# reel_schematic.net
KiCad netlist of a schematic drawn in EAGLE
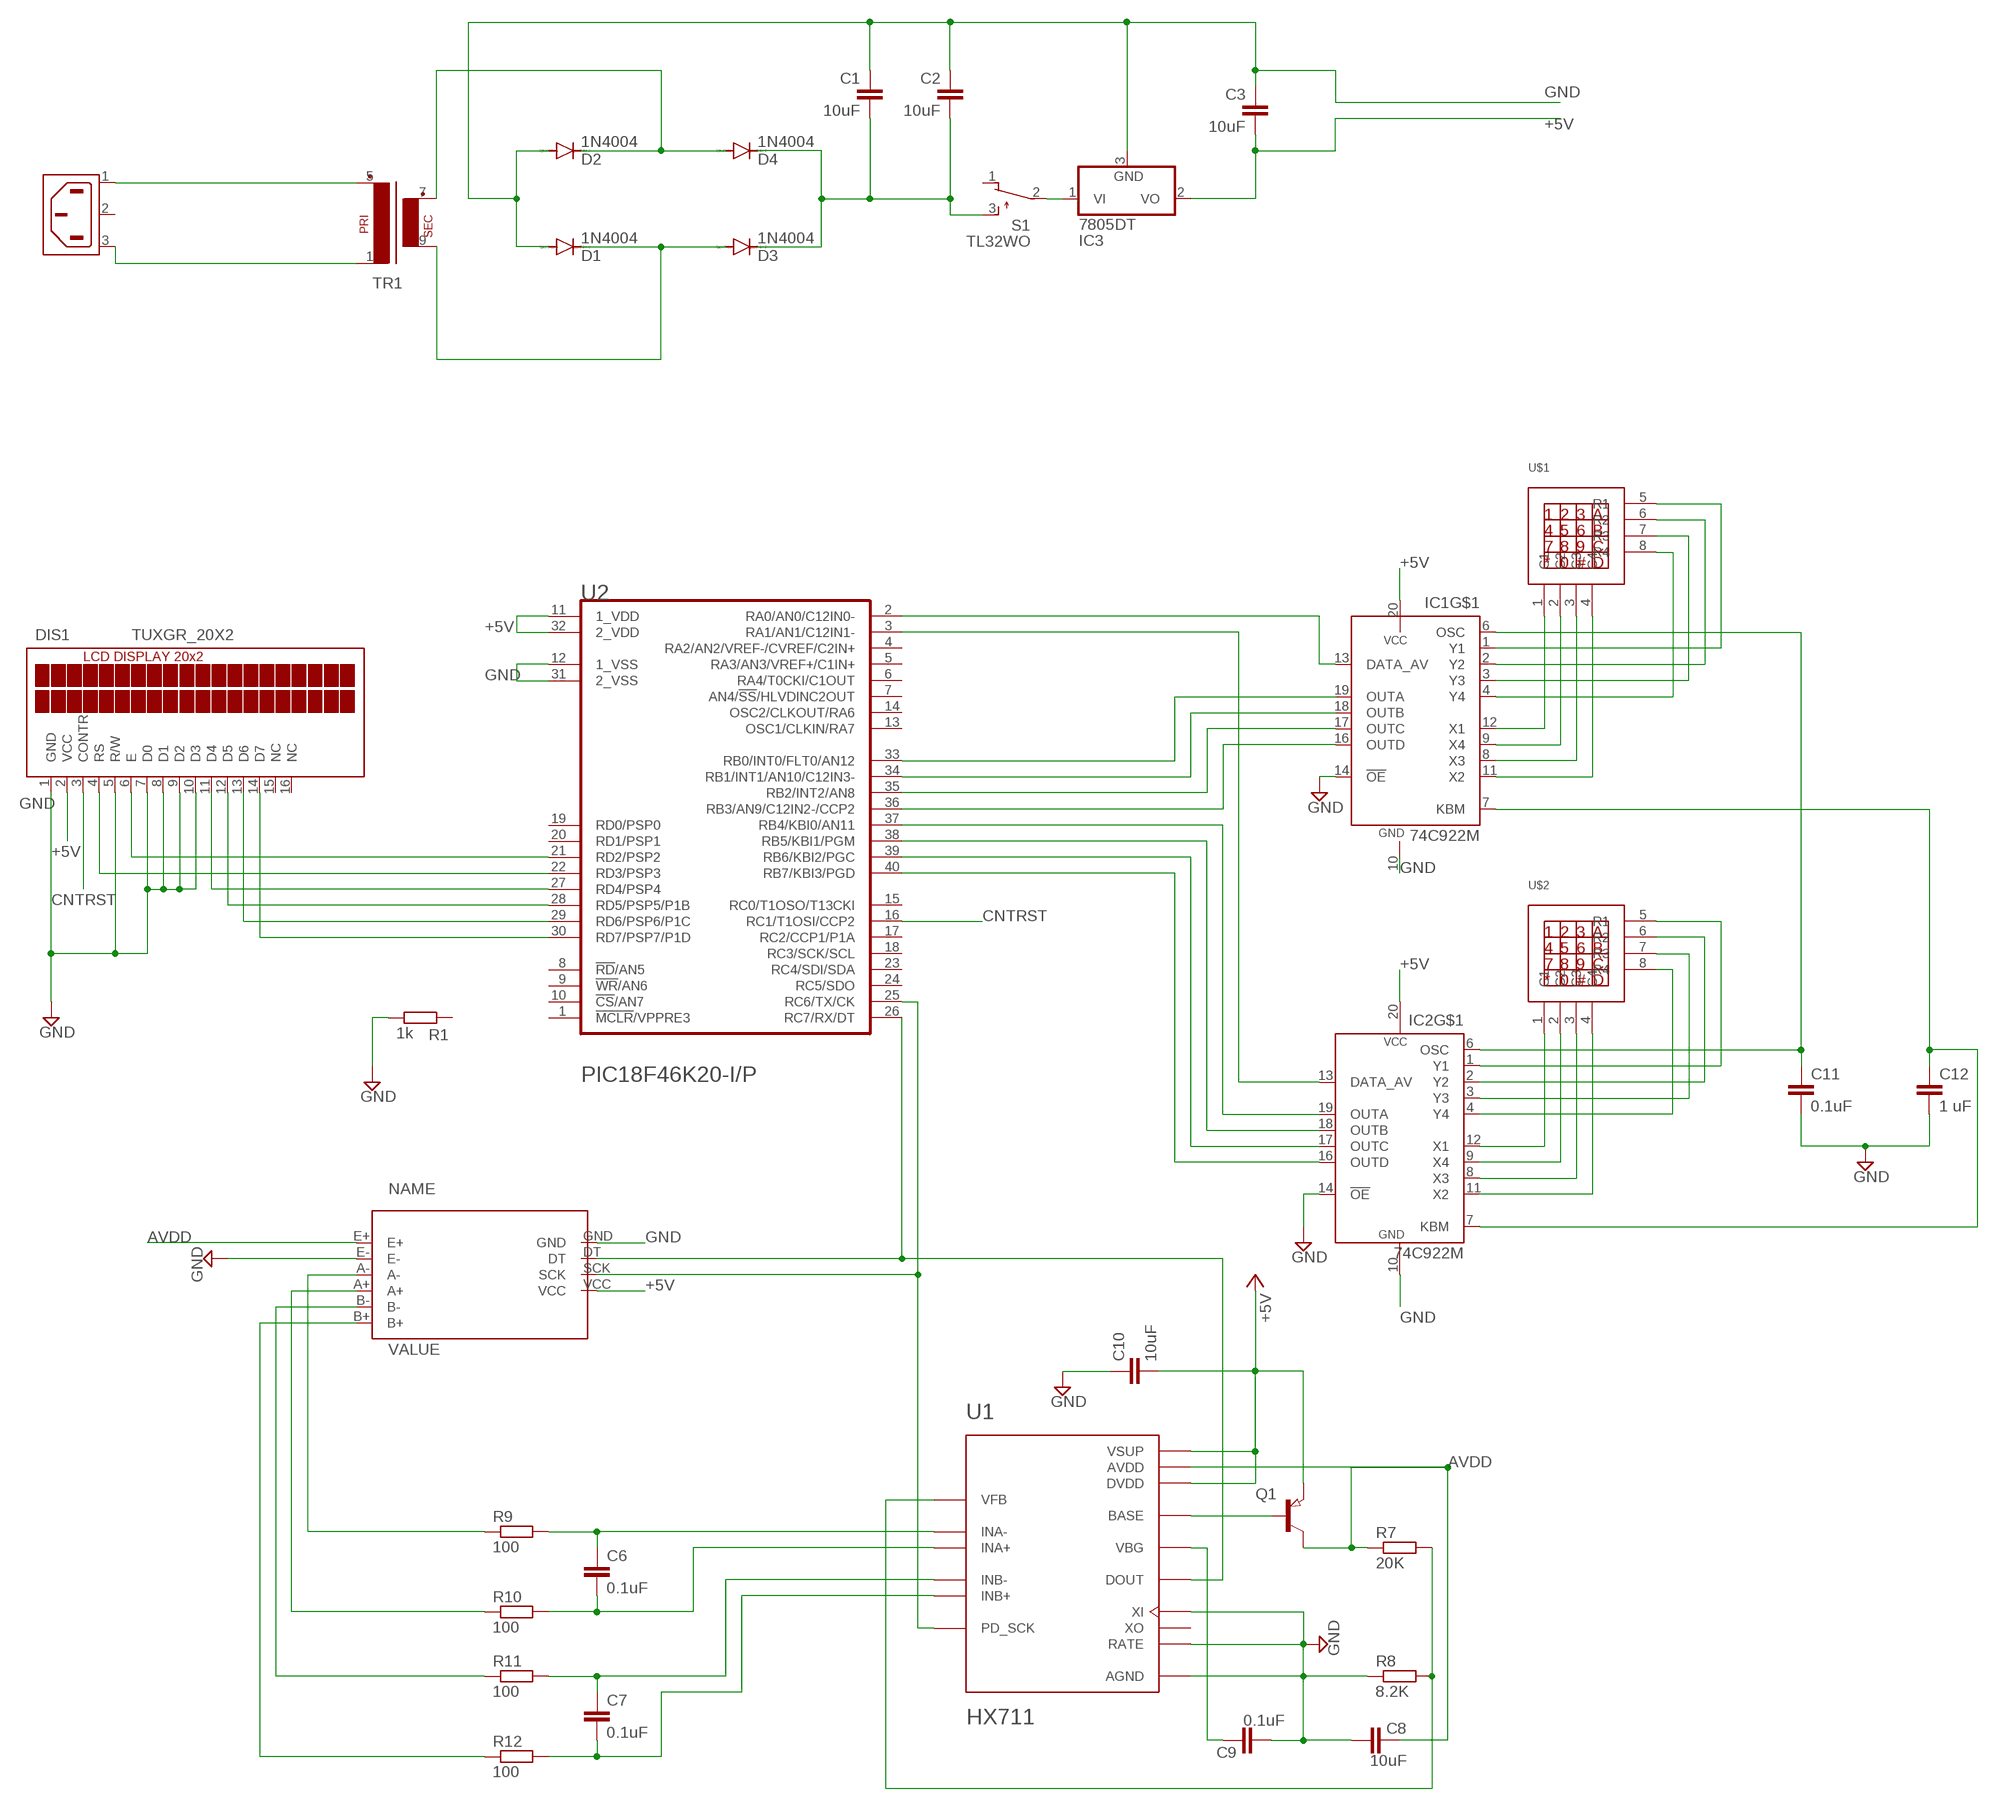
[diagram p0: schematic, sheet 1]

(export (version "E")
  (design (tool "Eeschema 10.0.6"))
  (components
    (comp (ref "C1")
      (value "10uF")
      (footprint "eagle-import:C2.5-2")
      (libsource (lib "eagle-import") (part "C2.5/2"))
    )
    (comp (ref "C2")
      (value "10uF")
      (footprint "eagle-import:C2.5-2")
      (libsource (lib "eagle-import") (part "C2.5/2"))
    )
    (comp (ref "C3")
      (value "10uF")
      (footprint "eagle-import:C2.5-2")
      (libsource (lib "eagle-import") (part "C2.5/2"))
    )
    (comp (ref "C6")
      (value "0.1uF")
      (footprint "eagle-import:C2.5-2")
      (libsource (lib "eagle-import") (part "C2.5/2"))
    )
    (comp (ref "C7")
      (value "0.1uF")
      (footprint "eagle-import:C2.5-2")
      (libsource (lib "eagle-import") (part "C2.5/2"))
    )
    (comp (ref "C8")
      (value "10uF")
      (footprint "eagle-import:C2.5-2")
      (libsource (lib "eagle-import") (part "C2.5/2"))
    )
    (comp (ref "C9")
      (value "0.1uF")
      (footprint "eagle-import:C2.5-2")
      (libsource (lib "eagle-import") (part "C2.5/2"))
    )
    (comp (ref "C10")
      (value "10uF")
      (footprint "eagle-import:C2.5-2")
      (libsource (lib "eagle-import") (part "C2.5/2"))
    )
    (comp (ref "C11")
      (value "0.1uF")
      (footprint "eagle-import:C2.5-2")
      (libsource (lib "eagle-import") (part "C2.5/2"))
    )
    (comp (ref "C12")
      (value "1 uF")
      (footprint "eagle-import:C2.5-2")
      (libsource (lib "eagle-import") (part "C2.5/2"))
    )
    (comp (ref "D1")
      (value "1N4004")
      (footprint "eagle-import:DO41-10")
      (libsource (lib "eagle-import") (part "1N4004"))
    )
    (comp (ref "D2")
      (value "1N4004")
      (footprint "eagle-import:DO41-10")
      (libsource (lib "eagle-import") (part "1N4004"))
    )
    (comp (ref "D3")
      (value "1N4004")
      (footprint "eagle-import:DO41-10")
      (libsource (lib "eagle-import") (part "1N4004"))
    )
    (comp (ref "D4")
      (value "1N4004")
      (footprint "eagle-import:DO41-10")
      (libsource (lib "eagle-import") (part "1N4004"))
    )
    (comp (ref "DIS1")
      (value "TUXGR_20X2")
      (footprint "eagle-import:TUXGR_20X2")
      (libsource (lib "eagle-import") (part "TUXGR_20X2"))
    )
    (comp (ref "HX711MODULE")
      (value "hx")
      (footprint "eagle-import:HX711")
      (libsource (lib "eagle-import") (part "HX711A"))
    )
    (comp (ref "IC1")
      (value "74C922M")
      (footprint "eagle-import:SO20W")
      (libsource (lib "eagle-import") (part "74C922M"))
    )
    (comp (ref "IC2")
      (value "74C922M")
      (footprint "eagle-import:SO20W")
      (libsource (lib "eagle-import") (part "74C922M"))
    )
    (comp (ref "IC3")
      (value "7805DT")
      (footprint "eagle-import:TO252")
      (libsource (lib "eagle-import") (part "78DT05"))
    )
    (comp (ref "Q1")
      (value "PNP-TRANSISTOR_SOT23")
      (footprint "eagle-import:SOT23")
      (libsource (lib "eagle-import") (part "PNP-TRANSISTOR_SOT23"))
    )
    (comp (ref "R1")
      (value "1k")
      (footprint "eagle-import:R0603")
      (libsource (lib "eagle-import") (part "R-EU_R0603"))
    )
    (comp (ref "R7")
      (value "20K")
      (footprint "eagle-import:R0603")
      (libsource (lib "eagle-import") (part "R-EU_R0603"))
    )
    (comp (ref "R8")
      (value "8.2K")
      (footprint "eagle-import:R0603")
      (libsource (lib "eagle-import") (part "R-EU_R0603"))
    )
    (comp (ref "R9")
      (value "100")
      (footprint "eagle-import:R0603")
      (libsource (lib "eagle-import") (part "R-EU_R0603"))
    )
    (comp (ref "R10")
      (value "100")
      (footprint "eagle-import:R0603")
      (libsource (lib "eagle-import") (part "R-EU_R0603"))
    )
    (comp (ref "R11")
      (value "100")
      (footprint "eagle-import:R0603")
      (libsource (lib "eagle-import") (part "R-EU_R0603"))
    )
    (comp (ref "R12")
      (value "100")
      (footprint "eagle-import:R0603")
      (libsource (lib "eagle-import") (part "R-EU_R0603"))
    )
    (comp (ref "S1")
      (value "TL32WO")
      (footprint "eagle-import:TL3XWO")
      (libsource (lib "eagle-import") (part "TL32WO"))
    )
    (comp (ref "TR1")
      (value "EI30-1")
      (footprint "eagle-import:EI30-1")
      (libsource (lib "eagle-import") (part "EI30-1"))
    )
    (comp (ref "U$1")
      (value "KEYPAD4X4")
      (footprint "eagle-import:KEYPAD4X4")
      (libsource (lib "eagle-import") (part "KEYPAD4X4"))
    )
    (comp (ref "U$2")
      (value "KEYPAD4X4")
      (footprint "eagle-import:KEYPAD4X4")
      (libsource (lib "eagle-import") (part "KEYPAD4X4"))
    )
    (comp (ref "U1")
      (value "HX711")
      (footprint "eagle-import:SOP127P600X180-16N")
      (fields (field (name "MF") "AVIA SEMICONDUCTOR"))
      (libsource (lib "eagle-import") (part "HX711"))
    )
    (comp (ref "U2")
      (value "MICROCHIP_PIC18F46K20-I-PMICROCHIP_PIC18F46K20-I-P_0_0")
      (footprint "eagle-import:MICROCHIP_PIC18F46K20-I-P_0")
      (fields (field (name "MF") "Microchip") (field (name "MPN") "PIC18F46K20-I/P"))
      (libsource (lib "eagle-import") (part "MICROCHIP_PIC18F46K20-I-PMICROCHIP_PIC18F46K20-I-P_0_0"))
    )
    (comp (ref "X1")
      (value "6ESRM-P")
      (footprint "eagle-import:6ESRM-P")
      (fields (field (name "MF") "TYCO ELECTRONICS"))
      (libsource (lib "eagle-import") (part "6ESRM-P"))
    )
  )
  (nets
    (net (code "1") (name "+5V") (class "Default")
      (node (ref "C10") (pin "2") (pinfunction "2_2") (pintype "passive"))
      (node (ref "C3") (pin "2") (pinfunction "2_2") (pintype "passive"))
      (node (ref "DIS1") (pin "2") (pinfunction "VCC_2") (pintype "power_in"))
      (node (ref "HX711MODULE") (pin "VCC") (pinfunction "VCC_VCC") (pintype "bidirectional"))
      (node (ref "IC1") (pin "20") (pinfunction "VCC_20") (pintype "power_in"))
      (node (ref "IC2") (pin "20") (pinfunction "VCC_20") (pintype "power_in"))
      (node (ref "IC3") (pin "2") (pinfunction "VO_2") (pintype "passive"))
      (node (ref "Q1") (pin "2") (pinfunction "E_2") (pintype "passive"))
      (node (ref "U1") (pin "1") (pinfunction "VSUP_1") (pintype "power_in"))
      (node (ref "U1") (pin "16") (pinfunction "DVDD_16") (pintype "power_in"))
      (node (ref "U2") (pin "11") (pinfunction "1_VDD_11") (pintype "power_in"))
      (node (ref "U2") (pin "32") (pinfunction "2_VDD_32") (pintype "power_in"))
    )
    (net (code "2") (name "/AVDD") (class "Default")
      (node (ref "C8") (pin "1") (pinfunction "1_1") (pintype "passive"))
      (node (ref "HX711MODULE") (pin "E+") (pinfunction "E+_E+") (pintype "bidirectional"))
      (node (ref "Q1") (pin "3") (pinfunction "C_3") (pintype "passive"))
      (node (ref "R7") (pin "1") (pinfunction "1_1") (pintype "passive"))
      (node (ref "U1") (pin "3") (pinfunction "AVDD_3") (pintype "power_in"))
    )
    (net (code "3") (name "/CNTRST") (class "Default")
      (node (ref "DIS1") (pin "3") (pinfunction "CONTR_3") (pintype "input"))
      (node (ref "U2") (pin "16") (pinfunction "RC1/T1OSI/CCP2_16") (pintype "bidirectional"))
    )
    (net (code "4") (name "GND") (class "Default")
      (node (ref "C1") (pin "1") (pinfunction "1_1") (pintype "passive"))
      (node (ref "C10") (pin "1") (pinfunction "1_1") (pintype "passive"))
      (node (ref "C11") (pin "2") (pinfunction "2_2") (pintype "passive"))
      (node (ref "C12") (pin "2") (pinfunction "2_2") (pintype "passive"))
      (node (ref "C2") (pin "1") (pinfunction "1_1") (pintype "passive"))
      (node (ref "C3") (pin "1") (pinfunction "1_1") (pintype "passive"))
      (node (ref "C8") (pin "2") (pinfunction "2_2") (pintype "passive"))
      (node (ref "C9") (pin "2") (pinfunction "2_2") (pintype "passive"))
      (node (ref "D1") (pin "A") (pinfunction "A_A") (pintype "passive"))
      (node (ref "D2") (pin "A") (pinfunction "A_A") (pintype "passive"))
      (node (ref "DIS1") (pin "1") (pinfunction "GND_1") (pintype "power_in"))
      (node (ref "DIS1") (pin "10") (pinfunction "D3_10") (pintype "input"))
      (node (ref "DIS1") (pin "5") (pinfunction "R/W_5") (pintype "input"))
      (node (ref "DIS1") (pin "7") (pinfunction "D0_7") (pintype "input"))
      (node (ref "DIS1") (pin "8") (pinfunction "D1_8") (pintype "input"))
      (node (ref "DIS1") (pin "9") (pinfunction "D2_9") (pintype "input"))
      (node (ref "HX711MODULE") (pin "E-") (pinfunction "E-_E-") (pintype "bidirectional"))
      (node (ref "HX711MODULE") (pin "GND") (pinfunction "GND_GND") (pintype "bidirectional"))
      (node (ref "IC1") (pin "10") (pinfunction "GND_10") (pintype "power_in"))
      (node (ref "IC1") (pin "14") (pinfunction "~{OE}_14") (pintype "input"))
      (node (ref "IC2") (pin "10") (pinfunction "GND_10") (pintype "power_in"))
      (node (ref "IC2") (pin "14") (pinfunction "~{OE}_14") (pintype "input"))
      (node (ref "IC3") (pin "3") (pinfunction "GND_3") (pintype "passive"))
      (node (ref "R1") (pin "1") (pinfunction "1_1") (pintype "passive"))
      (node (ref "R8") (pin "1") (pinfunction "1_1") (pintype "passive"))
      (node (ref "U1") (pin "14") (pinfunction "XI_14") (pintype "input"))
      (node (ref "U1") (pin "15") (pinfunction "RATE_15") (pintype "input"))
      (node (ref "U1") (pin "5") (pinfunction "AGND_5") (pintype "power_in"))
      (node (ref "U2") (pin "12") (pinfunction "1_VSS_12") (pintype "power_in"))
      (node (ref "U2") (pin "31") (pinfunction "2_VSS_31") (pintype "power_in"))
    )
    (net (code "5") (name "Net-(DIS1-D4)") (class "Default")
      (node (ref "DIS1") (pin "11") (pinfunction "D4_11") (pintype "input"))
      (node (ref "U2") (pin "27") (pinfunction "RD4/PSP4_27") (pintype "bidirectional"))
    )
    (net (code "6") (name "Net-(DIS1-D5)") (class "Default")
      (node (ref "DIS1") (pin "12") (pinfunction "D5_12") (pintype "input"))
      (node (ref "U2") (pin "28") (pinfunction "RD5/PSP5/P1B_28") (pintype "bidirectional"))
    )
    (net (code "7") (name "Net-(DIS1-D6)") (class "Default")
      (node (ref "DIS1") (pin "13") (pinfunction "D6_13") (pintype "input"))
      (node (ref "U2") (pin "29") (pinfunction "RD6/PSP6/P1C_29") (pintype "bidirectional"))
    )
    (net (code "8") (name "Net-(DIS1-D7)") (class "Default")
      (node (ref "DIS1") (pin "14") (pinfunction "D7_14") (pintype "input"))
      (node (ref "U2") (pin "30") (pinfunction "RD7/PSP7/P1D_30") (pintype "bidirectional"))
    )
    (net (code "9") (name "Net-(DIS1-E)") (class "Default")
      (node (ref "DIS1") (pin "6") (pinfunction "E_6") (pintype "input"))
      (node (ref "U2") (pin "21") (pinfunction "RD2/PSP2_21") (pintype "bidirectional"))
    )
    (net (code "10") (name "Net-(DIS1-RS)") (class "Default")
      (node (ref "DIS1") (pin "4") (pinfunction "RS_4") (pintype "input"))
      (node (ref "U2") (pin "22") (pinfunction "RD3/PSP3_22") (pintype "bidirectional"))
    )
    (net (code "11") (name "Net-(HX711MODULE-PadA+)") (class "Default")
      (node (ref "HX711MODULE") (pin "A+") (pinfunction "A+_A+") (pintype "bidirectional"))
      (node (ref "R10") (pin "1") (pinfunction "1_1") (pintype "passive"))
    )
    (net (code "12") (name "Net-(HX711MODULE-PadA-)") (class "Default")
      (node (ref "HX711MODULE") (pin "A-") (pinfunction "A-_A-") (pintype "bidirectional"))
      (node (ref "R9") (pin "1") (pinfunction "1_1") (pintype "passive"))
    )
    (net (code "13") (name "Net-(HX711MODULE-PadB+)") (class "Default")
      (node (ref "HX711MODULE") (pin "B+") (pinfunction "B+_B+") (pintype "bidirectional"))
      (node (ref "R12") (pin "1") (pinfunction "1_1") (pintype "passive"))
    )
    (net (code "14") (name "Net-(HX711MODULE-PadB-)") (class "Default")
      (node (ref "HX711MODULE") (pin "B-") (pinfunction "B-_B-") (pintype "bidirectional"))
      (node (ref "R11") (pin "1") (pinfunction "1_1") (pintype "passive"))
    )
    (net (code "15") (name "Net-(IC1A-DATA_AV)") (class "Default")
      (node (ref "IC1") (pin "13") (pinfunction "DATA_AV_13") (pintype "output"))
      (node (ref "U2") (pin "2") (pinfunction "RA0/AN0/C12IN0-_2") (pintype "bidirectional"))
    )
    (net (code "16") (name "Net-(IC1A-KBM)") (class "Default")
      (node (ref "C12") (pin "1") (pinfunction "1_1") (pintype "passive"))
      (node (ref "IC1") (pin "7") (pinfunction "KBM_7") (pintype "input"))
      (node (ref "IC2") (pin "7") (pinfunction "KBM_7") (pintype "input"))
    )
    (net (code "17") (name "Net-(IC1A-OSC)") (class "Default")
      (node (ref "C11") (pin "1") (pinfunction "1_1") (pintype "passive"))
      (node (ref "IC1") (pin "6") (pinfunction "OSC_6") (pintype "input"))
      (node (ref "IC2") (pin "6") (pinfunction "OSC_6") (pintype "input"))
    )
    (net (code "18") (name "Net-(IC1A-OUTA)") (class "Default")
      (node (ref "IC1") (pin "19") (pinfunction "OUTA_19") (pintype "output"))
      (node (ref "U2") (pin "33") (pinfunction "RB0/INT0/FLT0/AN12_33") (pintype "bidirectional"))
    )
    (net (code "19") (name "Net-(IC1A-OUTB)") (class "Default")
      (node (ref "IC1") (pin "18") (pinfunction "OUTB_18") (pintype "output"))
      (node (ref "U2") (pin "34") (pinfunction "RB1/INT1/AN10/C12IN3-_34") (pintype "bidirectional"))
    )
    (net (code "20") (name "Net-(IC1A-OUTC)") (class "Default")
      (node (ref "IC1") (pin "17") (pinfunction "OUTC_17") (pintype "output"))
      (node (ref "U2") (pin "35") (pinfunction "RB2/INT2/AN8_35") (pintype "bidirectional"))
    )
    (net (code "21") (name "Net-(IC1A-OUTD)") (class "Default")
      (node (ref "IC1") (pin "16") (pinfunction "OUTD_16") (pintype "output"))
      (node (ref "U2") (pin "36") (pinfunction "RB3/AN9/C12IN2-/CCP2_36") (pintype "bidirectional"))
    )
    (net (code "22") (name "Net-(IC1A-X1)") (class "Default")
      (node (ref "IC1") (pin "12") (pinfunction "X1_12") (pintype "input"))
      (node (ref "U$1") (pin "1") (pinfunction "C1_1") (pintype "bidirectional"))
    )
    (net (code "23") (name "Net-(IC1A-X2)") (class "Default")
      (node (ref "IC1") (pin "11") (pinfunction "X2_11") (pintype "input"))
      (node (ref "U$1") (pin "4") (pinfunction "C4_4") (pintype "bidirectional"))
    )
    (net (code "24") (name "Net-(IC1A-X3)") (class "Default")
      (node (ref "IC1") (pin "8") (pinfunction "X3_8") (pintype "input"))
      (node (ref "U$1") (pin "3") (pinfunction "C3_3") (pintype "bidirectional"))
    )
    (net (code "25") (name "Net-(IC1A-X4)") (class "Default")
      (node (ref "IC1") (pin "9") (pinfunction "X4_9") (pintype "input"))
      (node (ref "U$1") (pin "2") (pinfunction "C2_2") (pintype "bidirectional"))
    )
    (net (code "26") (name "Net-(IC1A-Y1)") (class "Default")
      (node (ref "IC1") (pin "1") (pinfunction "Y1_1") (pintype "input"))
      (node (ref "U$1") (pin "5") (pinfunction "R1_5") (pintype "bidirectional"))
    )
    (net (code "27") (name "Net-(IC1A-Y2)") (class "Default")
      (node (ref "IC1") (pin "2") (pinfunction "Y2_2") (pintype "input"))
      (node (ref "U$1") (pin "6") (pinfunction "R2_6") (pintype "bidirectional"))
    )
    (net (code "28") (name "Net-(IC1A-Y3)") (class "Default")
      (node (ref "IC1") (pin "3") (pinfunction "Y3_3") (pintype "input"))
      (node (ref "U$1") (pin "7") (pinfunction "R3_7") (pintype "bidirectional"))
    )
    (net (code "29") (name "Net-(IC1A-Y4)") (class "Default")
      (node (ref "IC1") (pin "4") (pinfunction "Y4_4") (pintype "input"))
      (node (ref "U$1") (pin "8") (pinfunction "R4_8") (pintype "bidirectional"))
    )
    (net (code "30") (name "Net-(IC2A-DATA_AV)") (class "Default")
      (node (ref "IC2") (pin "13") (pinfunction "DATA_AV_13") (pintype "output"))
      (node (ref "U2") (pin "3") (pinfunction "RA1/AN1/C12IN1-_3") (pintype "bidirectional"))
    )
    (net (code "31") (name "Net-(IC2A-OUTA)") (class "Default")
      (node (ref "IC2") (pin "19") (pinfunction "OUTA_19") (pintype "output"))
      (node (ref "U2") (pin "37") (pinfunction "RB4/KBI0/AN11_37") (pintype "bidirectional"))
    )
    (net (code "32") (name "Net-(IC2A-OUTB)") (class "Default")
      (node (ref "IC2") (pin "18") (pinfunction "OUTB_18") (pintype "output"))
      (node (ref "U2") (pin "38") (pinfunction "RB5/KBI1/PGM_38") (pintype "bidirectional"))
    )
    (net (code "33") (name "Net-(IC2A-OUTC)") (class "Default")
      (node (ref "IC2") (pin "17") (pinfunction "OUTC_17") (pintype "output"))
      (node (ref "U2") (pin "39") (pinfunction "RB6/KBI2/PGC_39") (pintype "bidirectional"))
    )
    (net (code "34") (name "Net-(IC2A-OUTD)") (class "Default")
      (node (ref "IC2") (pin "16") (pinfunction "OUTD_16") (pintype "output"))
      (node (ref "U2") (pin "40") (pinfunction "RB7/KBI3/PGD_40") (pintype "bidirectional"))
    )
    (net (code "35") (name "Net-(IC2A-X1)") (class "Default")
      (node (ref "IC2") (pin "12") (pinfunction "X1_12") (pintype "input"))
      (node (ref "U$2") (pin "1") (pinfunction "C1_1") (pintype "bidirectional"))
    )
    (net (code "36") (name "Net-(IC2A-X2)") (class "Default")
      (node (ref "IC2") (pin "11") (pinfunction "X2_11") (pintype "input"))
      (node (ref "U$2") (pin "4") (pinfunction "C4_4") (pintype "bidirectional"))
    )
    (net (code "37") (name "Net-(IC2A-X3)") (class "Default")
      (node (ref "IC2") (pin "8") (pinfunction "X3_8") (pintype "input"))
      (node (ref "U$2") (pin "3") (pinfunction "C3_3") (pintype "bidirectional"))
    )
    (net (code "38") (name "Net-(IC2A-X4)") (class "Default")
      (node (ref "IC2") (pin "9") (pinfunction "X4_9") (pintype "input"))
      (node (ref "U$2") (pin "2") (pinfunction "C2_2") (pintype "bidirectional"))
    )
    (net (code "39") (name "Net-(IC2A-Y1)") (class "Default")
      (node (ref "IC2") (pin "1") (pinfunction "Y1_1") (pintype "input"))
      (node (ref "U$2") (pin "5") (pinfunction "R1_5") (pintype "bidirectional"))
    )
    (net (code "40") (name "Net-(IC2A-Y2)") (class "Default")
      (node (ref "IC2") (pin "2") (pinfunction "Y2_2") (pintype "input"))
      (node (ref "U$2") (pin "6") (pinfunction "R2_6") (pintype "bidirectional"))
    )
    (net (code "41") (name "Net-(IC2A-Y3)") (class "Default")
      (node (ref "IC2") (pin "3") (pinfunction "Y3_3") (pintype "input"))
      (node (ref "U$2") (pin "7") (pinfunction "R3_7") (pintype "bidirectional"))
    )
    (net (code "42") (name "Net-(IC2A-Y4)") (class "Default")
      (node (ref "IC2") (pin "4") (pinfunction "Y4_4") (pintype "input"))
      (node (ref "U$2") (pin "8") (pinfunction "R4_8") (pintype "bidirectional"))
    )
    (net (code "43") (name "Net-(IC3-VI)") (class "Default")
      (node (ref "IC3") (pin "1") (pinfunction "VI_1") (pintype "input"))
      (node (ref "S1") (pin "2") (pinfunction "P_2") (pintype "passive"))
    )
    (net (code "44") (name "Net-(Q1-B)") (class "Default")
      (node (ref "Q1") (pin "1") (pinfunction "B_1") (pintype "passive"))
      (node (ref "U1") (pin "2") (pinfunction "BASE_2") (pintype "output"))
    )
    (net (code "45") (name "Net-(S1-S)") (class "Default")
      (node (ref "C1") (pin "2") (pinfunction "2_2") (pintype "passive"))
      (node (ref "C2") (pin "2") (pinfunction "2_2") (pintype "passive"))
      (node (ref "D3") (pin "C") (pinfunction "C_C") (pintype "passive"))
      (node (ref "D4") (pin "C") (pinfunction "C_C") (pintype "passive"))
      (node (ref "S1") (pin "3") (pinfunction "S_3") (pintype "passive"))
    )
    (net (code "46") (name "Net-(TR1-P1)") (class "Default")
      (node (ref "TR1") (pin "1") (pinfunction "P1_1") (pintype "passive"))
      (node (ref "X1") (pin "3") (pinfunction "AC2_3") (pintype "passive"))
    )
    (net (code "47") (name "Net-(TR1-P2)") (class "Default")
      (node (ref "TR1") (pin "5") (pinfunction "P2_5") (pintype "passive"))
      (node (ref "X1") (pin "1") (pinfunction "AC1_1") (pintype "passive"))
    )
    (net (code "48") (name "Net-(TR1-S3)") (class "Default")
      (node (ref "D2") (pin "C") (pinfunction "C_C") (pintype "passive"))
      (node (ref "D4") (pin "A") (pinfunction "A_A") (pintype "passive"))
      (node (ref "TR1") (pin "7") (pinfunction "S3_7") (pintype "passive"))
    )
    (net (code "49") (name "Net-(TR1-S4)") (class "Default")
      (node (ref "D1") (pin "C") (pinfunction "C_C") (pintype "passive"))
      (node (ref "D3") (pin "A") (pinfunction "A_A") (pintype "passive"))
      (node (ref "TR1") (pin "9") (pinfunction "S4_9") (pintype "passive"))
    )
    (net (code "50") (name "Net-(U1-DOUT)") (class "Default")
      (node (ref "HX711MODULE") (pin "DT") (pinfunction "DT_DT") (pintype "bidirectional"))
      (node (ref "U1") (pin "12") (pinfunction "DOUT_12") (pintype "output"))
      (node (ref "U2") (pin "26") (pinfunction "RC7/RX/DT_26") (pintype "bidirectional"))
    )
    (net (code "51") (name "Net-(U1-INA+)") (class "Default")
      (node (ref "C6") (pin "2") (pinfunction "2_2") (pintype "passive"))
      (node (ref "R10") (pin "2") (pinfunction "2_2") (pintype "passive"))
      (node (ref "U1") (pin "8") (pinfunction "INA+_8") (pintype "input"))
    )
    (net (code "52") (name "Net-(U1-INA-)") (class "Default")
      (node (ref "C6") (pin "1") (pinfunction "1_1") (pintype "passive"))
      (node (ref "R9") (pin "2") (pinfunction "2_2") (pintype "passive"))
      (node (ref "U1") (pin "7") (pinfunction "INA-_7") (pintype "input"))
    )
    (net (code "53") (name "Net-(U1-INB+)") (class "Default")
      (node (ref "C7") (pin "2") (pinfunction "2_2") (pintype "passive"))
      (node (ref "R12") (pin "2") (pinfunction "2_2") (pintype "passive"))
      (node (ref "U1") (pin "10") (pinfunction "INB+_10") (pintype "input"))
    )
    (net (code "54") (name "Net-(U1-INB-)") (class "Default")
      (node (ref "C7") (pin "1") (pinfunction "1_1") (pintype "passive"))
      (node (ref "R11") (pin "2") (pinfunction "2_2") (pintype "passive"))
      (node (ref "U1") (pin "9") (pinfunction "INB-_9") (pintype "input"))
    )
    (net (code "55") (name "Net-(U1-PD_SCK)") (class "Default")
      (node (ref "HX711MODULE") (pin "SCK") (pinfunction "SCK_SCK") (pintype "bidirectional"))
      (node (ref "U1") (pin "11") (pinfunction "PD_SCK_11") (pintype "input"))
      (node (ref "U2") (pin "25") (pinfunction "RC6/TX/CK_25") (pintype "bidirectional"))
    )
    (net (code "56") (name "Net-(U1-VBG)") (class "Default")
      (node (ref "C9") (pin "1") (pinfunction "1_1") (pintype "passive"))
      (node (ref "U1") (pin "6") (pinfunction "VBG_6") (pintype "output"))
    )
    (net (code "57") (name "Net-(U1-VFB)") (class "Default")
      (node (ref "R7") (pin "2") (pinfunction "2_2") (pintype "passive"))
      (node (ref "R8") (pin "2") (pinfunction "2_2") (pintype "passive"))
      (node (ref "U1") (pin "4") (pinfunction "VFB_4") (pintype "input"))
    )
    (net (code "58") (name "unconnected-(DIS1-NC-Pad15)") (class "Default")
      (node (ref "DIS1") (pin "15") (pinfunction "NC_15") (pintype "no_connect"))
    )
    (net (code "59") (name "unconnected-(DIS1-NC-Pad16)") (class "Default")
      (node (ref "DIS1") (pin "16") (pinfunction "NC_16") (pintype "no_connect"))
    )
    (net (code "60") (name "unconnected-(R1-Pad2)") (class "Default")
      (node (ref "R1") (pin "2") (pinfunction "2_2") (pintype "passive"))
    )
    (net (code "61") (name "unconnected-(S1-O-Pad1)") (class "Default")
      (node (ref "S1") (pin "1") (pinfunction "O_1") (pintype "passive"))
    )
    (net (code "62") (name "unconnected-(U1-XO-Pad13)") (class "Default")
      (node (ref "U1") (pin "13") (pinfunction "XO_13") (pintype "output"))
    )
    (net (code "63") (name "unconnected-(U2-AN4{slash}~{SS}{slash}HLVDINC2OUT-Pad7)") (class "Default")
      (node (ref "U2") (pin "7") (pinfunction "AN4/~{SS}/HLVDINC2OUT_7") (pintype "bidirectional"))
    )
    (net (code "64") (name "unconnected-(U2-OSC1{slash}CLKIN{slash}RA7-Pad13)") (class "Default")
      (node (ref "U2") (pin "13") (pinfunction "OSC1/CLKIN/RA7_13") (pintype "bidirectional"))
    )
    (net (code "65") (name "unconnected-(U2-OSC2{slash}CLKOUT{slash}RA6-Pad14)") (class "Default")
      (node (ref "U2") (pin "14") (pinfunction "OSC2/CLKOUT/RA6_14") (pintype "bidirectional"))
    )
    (net (code "66") (name "unconnected-(U2-RA2{slash}AN2{slash}VREF-{slash}CVREF{slash}C2IN+-Pad4)") (class "Default")
      (node (ref "U2") (pin "4") (pinfunction "RA2/AN2/VREF-/CVREF/C2IN+_4") (pintype "bidirectional"))
    )
    (net (code "67") (name "unconnected-(U2-RA3{slash}AN3{slash}VREF+{slash}C1IN+-Pad5)") (class "Default")
      (node (ref "U2") (pin "5") (pinfunction "RA3/AN3/VREF+/C1IN+_5") (pintype "bidirectional"))
    )
    (net (code "68") (name "unconnected-(U2-RA4{slash}T0CKI{slash}C1OUT-Pad6)") (class "Default")
      (node (ref "U2") (pin "6") (pinfunction "RA4/T0CKI/C1OUT_6") (pintype "bidirectional"))
    )
    (net (code "69") (name "unconnected-(U2-RC0{slash}T1OSO{slash}T13CKI-Pad15)") (class "Default")
      (node (ref "U2") (pin "15") (pinfunction "RC0/T1OSO/T13CKI_15") (pintype "bidirectional"))
    )
    (net (code "70") (name "unconnected-(U2-RC2{slash}CCP1{slash}P1A-Pad17)") (class "Default")
      (node (ref "U2") (pin "17") (pinfunction "RC2/CCP1/P1A_17") (pintype "bidirectional"))
    )
    (net (code "71") (name "unconnected-(U2-RC3{slash}SCK{slash}SCL-Pad18)") (class "Default")
      (node (ref "U2") (pin "18") (pinfunction "RC3/SCK/SCL_18") (pintype "bidirectional"))
    )
    (net (code "72") (name "unconnected-(U2-RC4{slash}SDI{slash}SDA-Pad23)") (class "Default")
      (node (ref "U2") (pin "23") (pinfunction "RC4/SDI/SDA_23") (pintype "bidirectional"))
    )
    (net (code "73") (name "unconnected-(U2-RC5{slash}SDO-Pad24)") (class "Default")
      (node (ref "U2") (pin "24") (pinfunction "RC5/SDO_24") (pintype "bidirectional"))
    )
    (net (code "74") (name "unconnected-(U2-RD0{slash}PSP0-Pad19)") (class "Default")
      (node (ref "U2") (pin "19") (pinfunction "RD0/PSP0_19") (pintype "bidirectional"))
    )
    (net (code "75") (name "unconnected-(U2-RD1{slash}PSP1-Pad20)") (class "Default")
      (node (ref "U2") (pin "20") (pinfunction "RD1/PSP1_20") (pintype "bidirectional"))
    )
    (net (code "76") (name "unconnected-(U2-~{CS}{slash}AN7-Pad10)") (class "Default")
      (node (ref "U2") (pin "10") (pinfunction "~{CS}/AN7_10") (pintype "bidirectional"))
    )
    (net (code "77") (name "unconnected-(U2-~{MCLR}{slash}VPPRE3-Pad1)") (class "Default")
      (node (ref "U2") (pin "1") (pinfunction "~{MCLR}/VPPRE3_1") (pintype "input"))
    )
    (net (code "78") (name "unconnected-(U2-~{RD}{slash}AN5-Pad8)") (class "Default")
      (node (ref "U2") (pin "8") (pinfunction "~{RD}/AN5_8") (pintype "bidirectional"))
    )
    (net (code "79") (name "unconnected-(U2-~{WR}{slash}AN6-Pad9)") (class "Default")
      (node (ref "U2") (pin "9") (pinfunction "~{WR}/AN6_9") (pintype "bidirectional"))
    )
    (net (code "80") (name "unconnected-(X1-SH-Pad2)") (class "Default")
      (node (ref "X1") (pin "2") (pinfunction "SH_2") (pintype "passive"))
    )
  )
)
